# Board.net
KiCad netlist of a schematic drawn in EAGLE
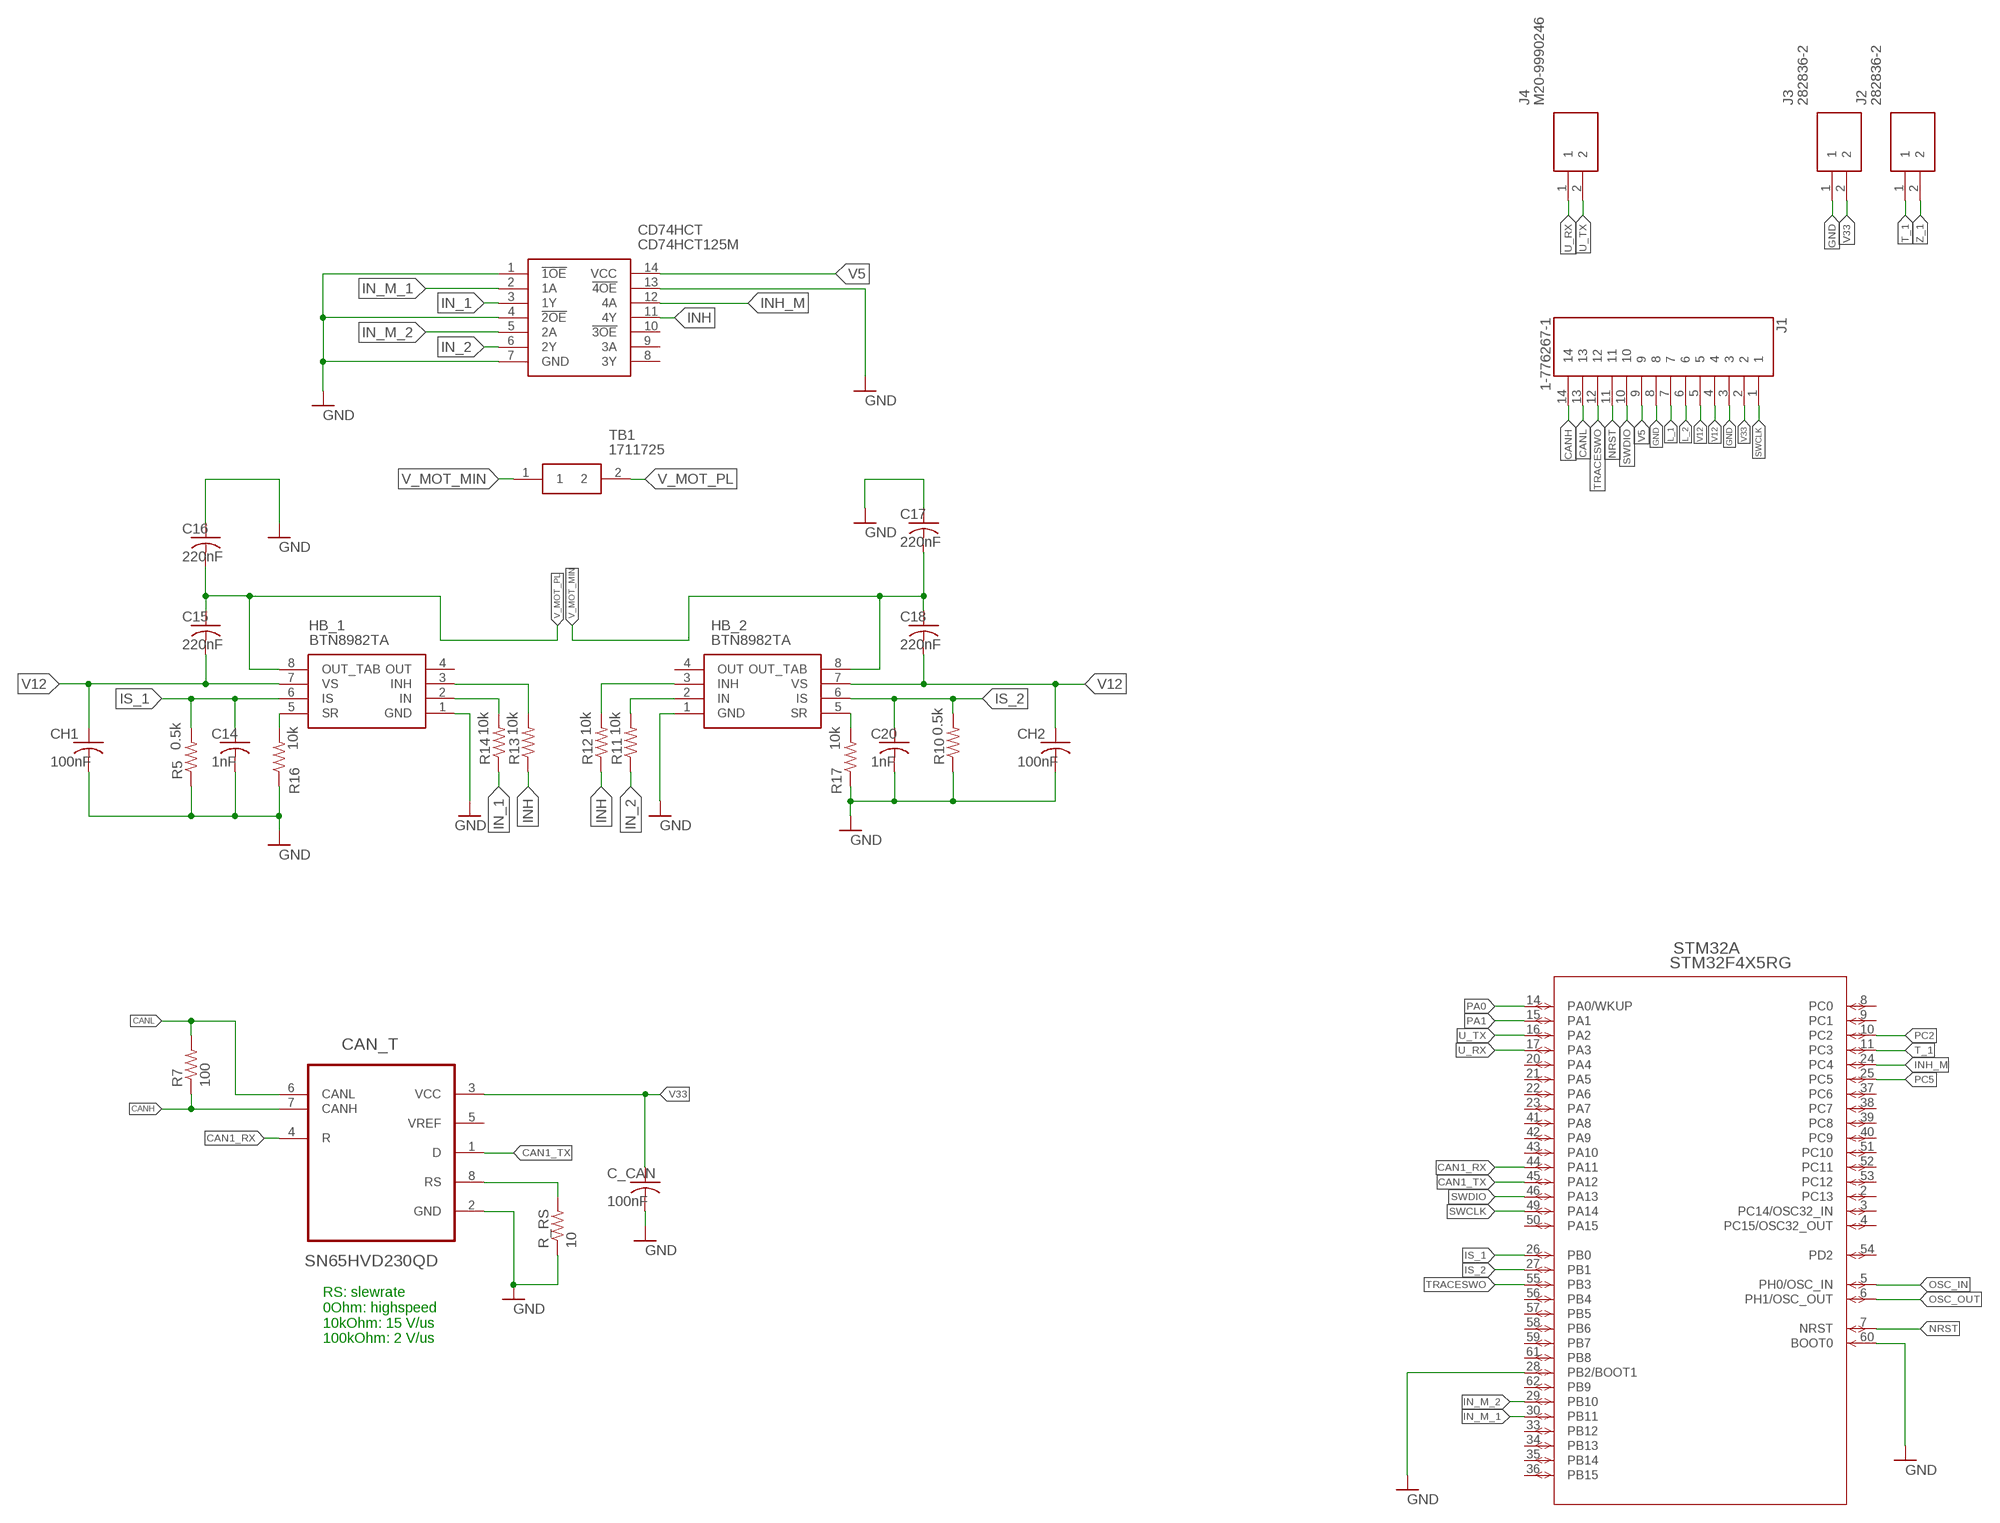
[diagram p0: schematic, sheet 1, part 1 of 2]
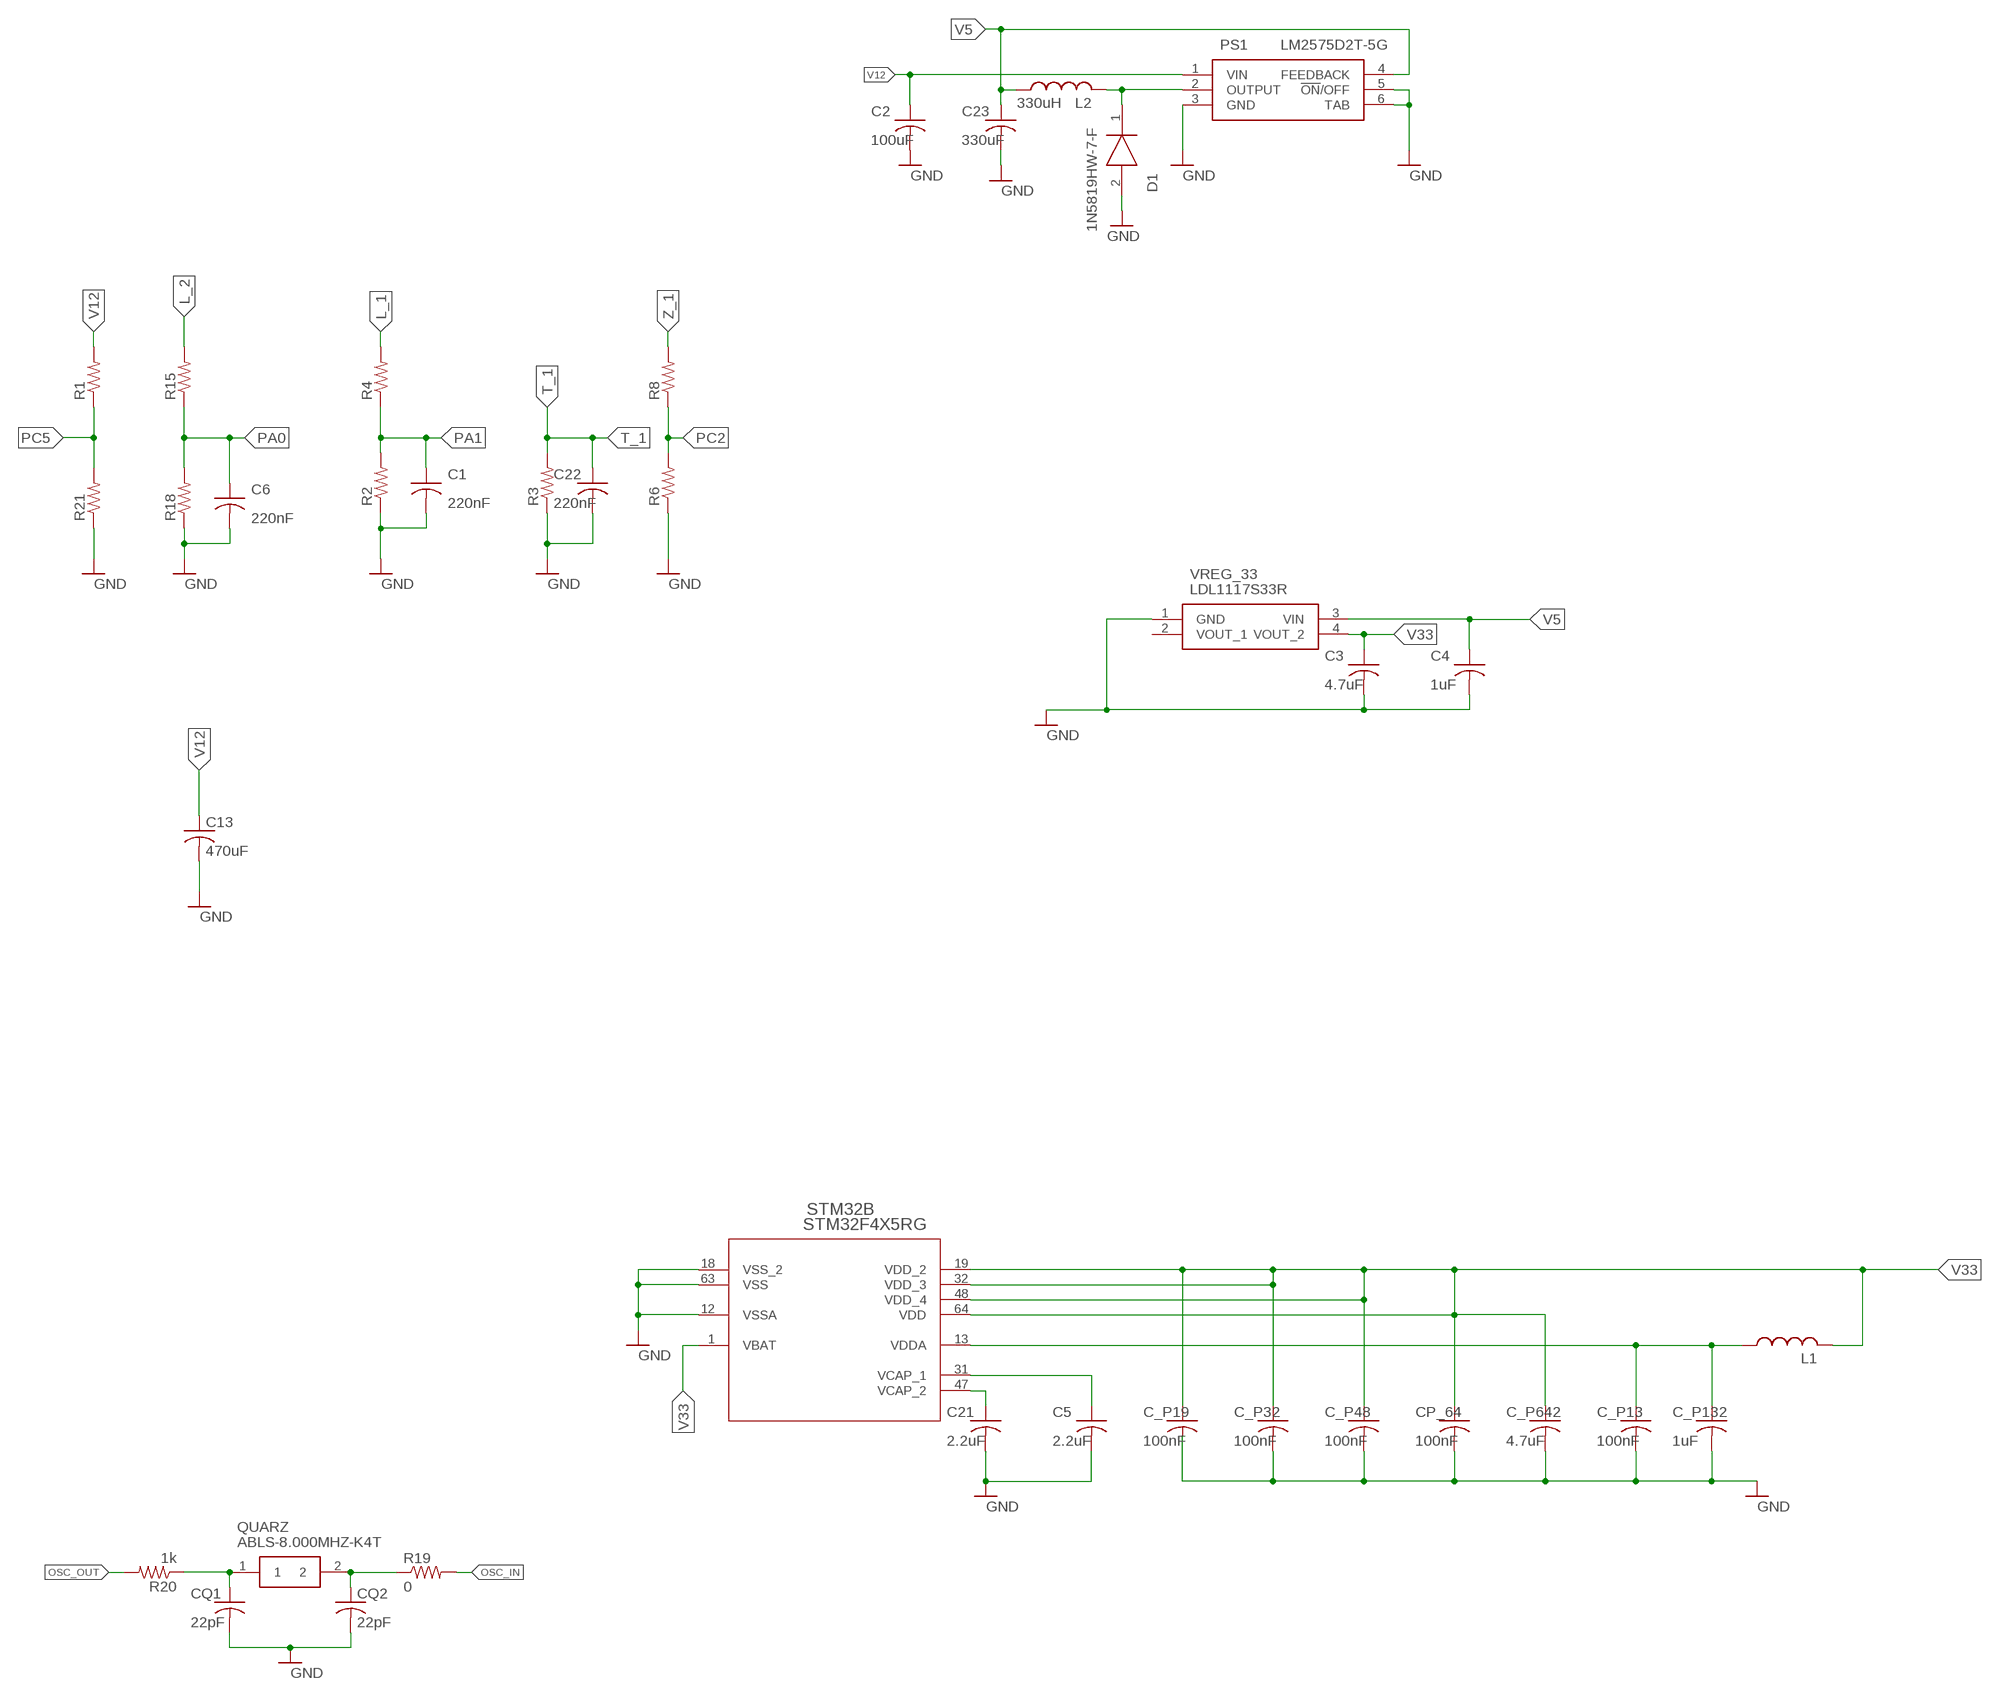
[diagram p1: schematic, sheet 1, part 2 of 2]

(export (version "E")
  (design (tool "Eeschema 10.0.6"))
  (components
    (comp (ref "C1")
      (value "220nF")
      (footprint "eagle-import:C0805")
      (libsource (lib "eagle-import") (part "C-USC0805"))
    )
    (comp (ref "C2")
      (value "100uF")
      (footprint "eagle-import:C0805")
      (libsource (lib "eagle-import") (part "C-USC0805"))
    )
    (comp (ref "C3")
      (value "4.7uF")
      (footprint "eagle-import:C0805")
      (libsource (lib "eagle-import") (part "C-USC0805"))
    )
    (comp (ref "C4")
      (value "1uF")
      (footprint "eagle-import:C0805")
      (libsource (lib "eagle-import") (part "C-USC0805"))
    )
    (comp (ref "C5")
      (value "2.2uF")
      (footprint "eagle-import:C0805")
      (libsource (lib "eagle-import") (part "C-USC0805"))
    )
    (comp (ref "C6")
      (value "220nF")
      (footprint "eagle-import:C0805")
      (libsource (lib "eagle-import") (part "C-USC0805"))
    )
    (comp (ref "C13")
      (value "470uF")
      (footprint "eagle-import:C050-075X075")
      (libsource (lib "eagle-import") (part "C-US050-075X075"))
    )
    (comp (ref "C14")
      (value "1nF")
      (footprint "eagle-import:C0805")
      (libsource (lib "eagle-import") (part "C-USC0805"))
    )
    (comp (ref "C15")
      (value "220nF")
      (footprint "eagle-import:C0805")
      (libsource (lib "eagle-import") (part "C-USC0805"))
    )
    (comp (ref "C16")
      (value "220nF")
      (footprint "eagle-import:C0805")
      (libsource (lib "eagle-import") (part "C-USC0805"))
    )
    (comp (ref "C17")
      (value "220nF")
      (footprint "eagle-import:C0805")
      (libsource (lib "eagle-import") (part "C-USC0805"))
    )
    (comp (ref "C18")
      (value "220nF")
      (footprint "eagle-import:C0805")
      (libsource (lib "eagle-import") (part "C-USC0805"))
    )
    (comp (ref "C20")
      (value "1nF")
      (footprint "eagle-import:C0805")
      (libsource (lib "eagle-import") (part "C-USC0805"))
    )
    (comp (ref "C21")
      (value "2.2uF")
      (footprint "eagle-import:C0805")
      (libsource (lib "eagle-import") (part "C-USC0805"))
    )
    (comp (ref "C22")
      (value "220nF")
      (footprint "eagle-import:C0805")
      (libsource (lib "eagle-import") (part "C-USC0805"))
    )
    (comp (ref "C23")
      (value "330uF")
      (footprint "eagle-import:C0805")
      (libsource (lib "eagle-import") (part "C-USC0805"))
    )
    (comp (ref "CAN_T")
      (value "SN65HVD230QD")
      (footprint "eagle-import:SOIC127P600X175-8N")
      (fields (field (name "MF") "TEXAS INSTRUMENTS") (field (name "MPN") "SN65HVD230QD.."))
      (libsource (lib "eagle-import") (part "SN65HVD230QD"))
    )
    (comp (ref "CD74HCT")
      (value "CD74HCT125M")
      (footprint "eagle-import:SOIC127P600X175-14N")
      (fields (field (name "MOUSER_PART_NUMBER") "595-CD74HCT125M"))
      (libsource (lib "eagle-import") (part "CD74HCT125M"))
    )
    (comp (ref "CH1")
      (value "100nF")
      (footprint "eagle-import:C0805")
      (libsource (lib "eagle-import") (part "C-USC0805"))
    )
    (comp (ref "CH2")
      (value "100nF")
      (footprint "eagle-import:C0805")
      (libsource (lib "eagle-import") (part "C-USC0805"))
    )
    (comp (ref "CP_64")
      (value "100nF")
      (footprint "eagle-import:C0805")
      (libsource (lib "eagle-import") (part "C-USC0805"))
    )
    (comp (ref "CQ1")
      (value "22pF")
      (footprint "eagle-import:C0805")
      (libsource (lib "eagle-import") (part "C-USC0805"))
    )
    (comp (ref "CQ2")
      (value "22pF")
      (footprint "eagle-import:C0805")
      (libsource (lib "eagle-import") (part "C-USC0805"))
    )
    (comp (ref "C_CAN")
      (value "100nF")
      (footprint "eagle-import:C0805")
      (libsource (lib "eagle-import") (part "C-USC0805"))
    )
    (comp (ref "C_P13")
      (value "100nF")
      (footprint "eagle-import:C0805")
      (libsource (lib "eagle-import") (part "C-USC0805"))
    )
    (comp (ref "C_P19")
      (value "100nF")
      (footprint "eagle-import:C0805")
      (libsource (lib "eagle-import") (part "C-USC0805"))
    )
    (comp (ref "C_P32")
      (value "100nF")
      (footprint "eagle-import:C0805")
      (libsource (lib "eagle-import") (part "C-USC0805"))
    )
    (comp (ref "C_P48")
      (value "100nF")
      (footprint "eagle-import:C0805")
      (libsource (lib "eagle-import") (part "C-USC0805"))
    )
    (comp (ref "C_P132")
      (value "1uF")
      (footprint "eagle-import:C0805")
      (libsource (lib "eagle-import") (part "C-USC0805"))
    )
    (comp (ref "C_P642")
      (value "4.7uF")
      (footprint "eagle-import:C0805")
      (libsource (lib "eagle-import") (part "C-USC0805"))
    )
    (comp (ref "D1")
      (value "1N5819HW-7-F")
      (footprint "eagle-import:SOD3716X145N")
      (fields (field (name "MOUSER_PART_NUMBER") "621-1N5819HW-F"))
      (libsource (lib "eagle-import") (part "1N5819HW-7-F"))
    )
    (comp (ref "HB_1")
      (value "BTN8982TA")
      (footprint "eagle-import:TO127P1500X440-8N")
      (fields (field (name "MOUSER_PART_NUMBER") "726-BTN8982TA"))
      (libsource (lib "eagle-import") (part "BTN8982TA"))
    )
    (comp (ref "HB_2")
      (value "BTN8982TA")
      (footprint "eagle-import:TO127P1500X440-8N")
      (fields (field (name "MOUSER_PART_NUMBER") "726-BTN8982TA"))
      (libsource (lib "eagle-import") (part "BTN8982TA"))
    )
    (comp (ref "J1")
      (value "1-776267-1")
      (footprint "eagle-import:TE_1-776267-1")
      (fields (field (name "DIGI-KEY_PART_NUMBER") "A142413-ND") (field (name "MF") "TE Connectivity"))
      (libsource (lib "eagle-import") (part "1-776267-1"))
    )
    (comp (ref "J2")
      (value "282836-2")
      (footprint "eagle-import:SHDR2W100P0X500_1X2_1000X820X1")
      (fields (field (name "MOUSER_PART_NUMBER") "571-2828362"))
      (libsource (lib "eagle-import") (part "282836-2"))
    )
    (comp (ref "J3")
      (value "282836-2")
      (footprint "eagle-import:SHDR2W100P0X500_1X2_1000X820X1")
      (fields (field (name "MOUSER_PART_NUMBER") "571-2828362"))
      (libsource (lib "eagle-import") (part "282836-2"))
    )
    (comp (ref "J4")
      (value "M20-9990246")
      (footprint "eagle-import:HDRV2W64P0X254_1X2_508X254X864")
      (fields (field (name "MOUSER_PART_NUMBER") "855-M20-9990246"))
      (libsource (lib "eagle-import") (part "M20-9990246"))
    )
    (comp (ref "L1")
      (value "INDUCTOR_0805_N")
      (footprint "eagle-import:RESC0805_N")
      (libsource (lib "eagle-import") (part "INDUCTOR_0805_N"))
    )
    (comp (ref "L2")
      (value "330uH")
      (footprint "eagle-import:RESC0805_N")
      (libsource (lib "eagle-import") (part "INDUCTOR_0805_N"))
    )
    (comp (ref "PS1")
      (value "LM2575D2T-5G")
      (footprint "eagle-import:D2TSUFFIX-CASE936A-02-ISSUEC")
      (fields (field (name "MOUSER_PART_NUMBER") "863-LM2575D2T-5G"))
      (libsource (lib "eagle-import") (part "LM2575D2T-5G"))
    )
    (comp (ref "QUARZ")
      (value "ABLS-8.000MHZ-K4T")
      (footprint "eagle-import:ABLS-12.000MHZ-B2")
      (fields (field (name "MOUSER_PART_NUMBER") "815-ABLS-8.0MK4-T") (field (name "MF") "ABRACON"))
      (libsource (lib "eagle-import") (part "ABLS-8.000MHZ-K4T"))
    )
    (comp (ref "R1")
      (value "R-US_R0805")
      (footprint "eagle-import:R0805")
      (libsource (lib "eagle-import") (part "R-US_R0805"))
    )
    (comp (ref "R2")
      (value "R-US_R0805")
      (footprint "eagle-import:R0805")
      (libsource (lib "eagle-import") (part "R-US_R0805"))
    )
    (comp (ref "R3")
      (value "R-US_R0805")
      (footprint "eagle-import:R0805")
      (libsource (lib "eagle-import") (part "R-US_R0805"))
    )
    (comp (ref "R4")
      (value "R-US_R0805")
      (footprint "eagle-import:R0805")
      (libsource (lib "eagle-import") (part "R-US_R0805"))
    )
    (comp (ref "R5")
      (value "0.5k")
      (footprint "eagle-import:R0805")
      (libsource (lib "eagle-import") (part "R-US_R0805"))
    )
    (comp (ref "R6")
      (value "R-US_R0805")
      (footprint "eagle-import:R0805")
      (libsource (lib "eagle-import") (part "R-US_R0805"))
    )
    (comp (ref "R7")
      (value "100")
      (footprint "eagle-import:R0805")
      (libsource (lib "eagle-import") (part "R-US_R0805"))
    )
    (comp (ref "R8")
      (value "R-US_R0805")
      (footprint "eagle-import:R0805")
      (libsource (lib "eagle-import") (part "R-US_R0805"))
    )
    (comp (ref "R10")
      (value "0.5k")
      (footprint "eagle-import:R0805")
      (libsource (lib "eagle-import") (part "R-US_R0805"))
    )
    (comp (ref "R11")
      (value "10k")
      (footprint "eagle-import:R0805")
      (libsource (lib "eagle-import") (part "R-US_R0805"))
    )
    (comp (ref "R12")
      (value "10k")
      (footprint "eagle-import:R0805")
      (libsource (lib "eagle-import") (part "R-US_R0805"))
    )
    (comp (ref "R13")
      (value "10k")
      (footprint "eagle-import:R0805")
      (libsource (lib "eagle-import") (part "R-US_R0805"))
    )
    (comp (ref "R14")
      (value "10k")
      (footprint "eagle-import:R0805")
      (libsource (lib "eagle-import") (part "R-US_R0805"))
    )
    (comp (ref "R15")
      (value "R-US_R0805")
      (footprint "eagle-import:R0805")
      (libsource (lib "eagle-import") (part "R-US_R0805"))
    )
    (comp (ref "R16")
      (value "10k")
      (footprint "eagle-import:R0805")
      (libsource (lib "eagle-import") (part "resistor_348_R-US_R0805"))
    )
    (comp (ref "R17")
      (value "10k")
      (footprint "eagle-import:R0805")
      (libsource (lib "eagle-import") (part "resistor_348_R-US_R0805"))
    )
    (comp (ref "R18")
      (value "R-US_R0805")
      (footprint "eagle-import:R0805")
      (libsource (lib "eagle-import") (part "R-US_R0805"))
    )
    (comp (ref "R19")
      (value "0")
      (footprint "eagle-import:R0805")
      (libsource (lib "eagle-import") (part "resistor_348_R-US_R0805"))
    )
    (comp (ref "R20")
      (value "1k")
      (footprint "eagle-import:R0805")
      (libsource (lib "eagle-import") (part "resistor_348_R-US_R0805"))
    )
    (comp (ref "R21")
      (value "R-US_R0805")
      (footprint "eagle-import:R0805")
      (libsource (lib "eagle-import") (part "R-US_R0805"))
    )
    (comp (ref "R_RS")
      (value "10")
      (footprint "eagle-import:R0805")
      (libsource (lib "eagle-import") (part "R-US_R0805"))
    )
    (comp (ref "STM32")
      (value "STM32F4X5RG")
      (footprint "eagle-import:LQFP64-10X10MM")
      (fields (field (name "OC_FARNELL") "unknown"))
      (libsource (lib "eagle-import") (part "STM32F4X5RG"))
    )
    (comp (ref "TB1")
      (value "1711725")
      (footprint "eagle-import:PHEONIX-5.08PITCH-2PIN")
      (fields (field (name "MOUSER_PART_NUMBER") "651-1711725"))
      (libsource (lib "eagle-import") (part "1711725"))
    )
    (comp (ref "VREG_33")
      (value "LDL1117S33R")
      (footprint "eagle-import:SOT230P700X180-4N")
      (fields (field (name "MOUSER_PART_NUMBER") "511-LDL1117S33R") (field (name "MF") "STMICROELECTRONICS"))
      (libsource (lib "eagle-import") (part "LDL1117S33R"))
    )
  )
  (nets
    (net (code "1") (name "CAN1_RX") (class "Default")
      (node (ref "CAN_T") (pin "4") (pinfunction "R_4") (pintype "output"))
      (node (ref "STM32") (pin "44") (pinfunction "PA11_44") (pintype "bidirectional"))
    )
    (net (code "2") (name "CAN1_TX") (class "Default")
      (node (ref "CAN_T") (pin "1") (pinfunction "D_1") (pintype "input"))
      (node (ref "STM32") (pin "45") (pinfunction "PA12_45") (pintype "bidirectional"))
    )
    (net (code "3") (name "CANH") (class "Default")
      (node (ref "CAN_T") (pin "7") (pinfunction "CANH_7") (pintype "output"))
      (node (ref "J1") (pin "14") (pinfunction "14_14") (pintype "passive"))
      (node (ref "R7") (pin "1") (pinfunction "1_1") (pintype "passive"))
    )
    (net (code "4") (name "CANL") (class "Default")
      (node (ref "CAN_T") (pin "6") (pinfunction "CANL_6") (pintype "output"))
      (node (ref "J1") (pin "13") (pinfunction "13_13") (pintype "passive"))
      (node (ref "R7") (pin "2") (pinfunction "2_2") (pintype "passive"))
    )
    (net (code "5") (name "GND") (class "Default")
      (node (ref "C1") (pin "2") (pinfunction "2_2") (pintype "passive"))
      (node (ref "C13") (pin "2") (pinfunction "2_2") (pintype "passive"))
      (node (ref "C14") (pin "2") (pinfunction "2_2") (pintype "passive"))
      (node (ref "C16") (pin "1") (pinfunction "1_1") (pintype "passive"))
      (node (ref "C17") (pin "1") (pinfunction "1_1") (pintype "passive"))
      (node (ref "C2") (pin "2") (pinfunction "2_2") (pintype "passive"))
      (node (ref "C20") (pin "2") (pinfunction "2_2") (pintype "passive"))
      (node (ref "C21") (pin "2") (pinfunction "2_2") (pintype "passive"))
      (node (ref "C22") (pin "2") (pinfunction "2_2") (pintype "passive"))
      (node (ref "C23") (pin "2") (pinfunction "2_2") (pintype "passive"))
      (node (ref "C3") (pin "2") (pinfunction "2_2") (pintype "passive"))
      (node (ref "C4") (pin "2") (pinfunction "2_2") (pintype "passive"))
      (node (ref "C5") (pin "2") (pinfunction "2_2") (pintype "passive"))
      (node (ref "C6") (pin "2") (pinfunction "2_2") (pintype "passive"))
      (node (ref "CAN_T") (pin "2") (pinfunction "GND_2") (pintype "passive"))
      (node (ref "CD74HCT") (pin "1") (pinfunction "~{1OE}_1") (pintype "bidirectional"))
      (node (ref "CD74HCT") (pin "13") (pinfunction "~{4OE}_13") (pintype "bidirectional"))
      (node (ref "CD74HCT") (pin "4") (pinfunction "~{2OE}_4") (pintype "bidirectional"))
      (node (ref "CD74HCT") (pin "7") (pinfunction "GND_7") (pintype "power_in"))
      (node (ref "CH1") (pin "2") (pinfunction "2_2") (pintype "passive"))
      (node (ref "CH2") (pin "2") (pinfunction "2_2") (pintype "passive"))
      (node (ref "CP_64") (pin "2") (pinfunction "2_2") (pintype "passive"))
      (node (ref "CQ1") (pin "2") (pinfunction "2_2") (pintype "passive"))
      (node (ref "CQ2") (pin "2") (pinfunction "2_2") (pintype "passive"))
      (node (ref "C_CAN") (pin "2") (pinfunction "2_2") (pintype "passive"))
      (node (ref "C_P13") (pin "2") (pinfunction "2_2") (pintype "passive"))
      (node (ref "C_P132") (pin "2") (pinfunction "2_2") (pintype "passive"))
      (node (ref "C_P19") (pin "2") (pinfunction "2_2") (pintype "passive"))
      (node (ref "C_P32") (pin "2") (pinfunction "2_2") (pintype "passive"))
      (node (ref "C_P48") (pin "2") (pinfunction "2_2") (pintype "passive"))
      (node (ref "C_P642") (pin "2") (pinfunction "2_2") (pintype "passive"))
      (node (ref "D1") (pin "2") (pinfunction "A_2") (pintype "bidirectional"))
      (node (ref "HB_1") (pin "1") (pinfunction "GND_1") (pintype "power_in"))
      (node (ref "HB_2") (pin "1") (pinfunction "GND_1") (pintype "power_in"))
      (node (ref "J1") (pin "3") (pinfunction "3_3") (pintype "passive"))
      (node (ref "J1") (pin "8") (pinfunction "8_8") (pintype "passive"))
      (node (ref "J3") (pin "1") (pinfunction "1_1") (pintype "bidirectional"))
      (node (ref "PS1") (pin "3") (pinfunction "GND_3") (pintype "bidirectional"))
      (node (ref "PS1") (pin "5") (pinfunction "~{ON}/OFF_5") (pintype "bidirectional"))
      (node (ref "PS1") (pin "6") (pinfunction "TAB_6") (pintype "bidirectional"))
      (node (ref "R10") (pin "1") (pinfunction "1_1") (pintype "passive"))
      (node (ref "R16") (pin "1") (pinfunction "1_1") (pintype "passive"))
      (node (ref "R17") (pin "1") (pinfunction "1_1") (pintype "passive"))
      (node (ref "R18") (pin "1") (pinfunction "1_1") (pintype "passive"))
      (node (ref "R2") (pin "1") (pinfunction "1_1") (pintype "passive"))
      (node (ref "R21") (pin "1") (pinfunction "1_1") (pintype "passive"))
      (node (ref "R3") (pin "1") (pinfunction "1_1") (pintype "passive"))
      (node (ref "R5") (pin "1") (pinfunction "1_1") (pintype "passive"))
      (node (ref "R6") (pin "1") (pinfunction "1_1") (pintype "passive"))
      (node (ref "R_RS") (pin "1") (pinfunction "1_1") (pintype "passive"))
      (node (ref "STM32") (pin "12") (pinfunction "VSSA_12") (pintype "power_in"))
      (node (ref "STM32") (pin "18") (pinfunction "VSS_2_18") (pintype "power_in"))
      (node (ref "STM32") (pin "28") (pinfunction "PB2/BOOT1_28") (pintype "bidirectional"))
      (node (ref "STM32") (pin "60") (pinfunction "BOOT0_60") (pintype "input"))
      (node (ref "STM32") (pin "63") (pinfunction "VSS_63") (pintype "power_in"))
      (node (ref "VREG_33") (pin "1") (pinfunction "GND_1") (pintype "power_in"))
    )
    (net (code "6") (name "INH") (class "Default")
      (node (ref "CD74HCT") (pin "11") (pinfunction "4Y_11") (pintype "bidirectional"))
      (node (ref "R12") (pin "1") (pinfunction "1_1") (pintype "passive"))
      (node (ref "R13") (pin "1") (pinfunction "1_1") (pintype "passive"))
    )
    (net (code "7") (name "INH_M") (class "Default")
      (node (ref "CD74HCT") (pin "12") (pinfunction "4A_12") (pintype "bidirectional"))
      (node (ref "STM32") (pin "24") (pinfunction "PC4_24") (pintype "bidirectional"))
    )
    (net (code "8") (name "IN_1") (class "Default")
      (node (ref "CD74HCT") (pin "3") (pinfunction "1Y_3") (pintype "bidirectional"))
      (node (ref "R14") (pin "1") (pinfunction "1_1") (pintype "passive"))
    )
    (net (code "9") (name "IN_2") (class "Default")
      (node (ref "CD74HCT") (pin "6") (pinfunction "2Y_6") (pintype "bidirectional"))
      (node (ref "R11") (pin "1") (pinfunction "1_1") (pintype "passive"))
    )
    (net (code "10") (name "IN_M_1") (class "Default")
      (node (ref "CD74HCT") (pin "2") (pinfunction "1A_2") (pintype "bidirectional"))
      (node (ref "STM32") (pin "30") (pinfunction "PB11_30") (pintype "bidirectional"))
    )
    (net (code "11") (name "IN_M_2") (class "Default")
      (node (ref "CD74HCT") (pin "5") (pinfunction "2A_5") (pintype "bidirectional"))
      (node (ref "STM32") (pin "29") (pinfunction "PB10_29") (pintype "bidirectional"))
    )
    (net (code "12") (name "IS_1") (class "Default")
      (node (ref "C14") (pin "1") (pinfunction "1_1") (pintype "passive"))
      (node (ref "HB_1") (pin "6") (pinfunction "IS_6") (pintype "bidirectional"))
      (node (ref "R5") (pin "2") (pinfunction "2_2") (pintype "passive"))
      (node (ref "STM32") (pin "26") (pinfunction "PB0_26") (pintype "bidirectional"))
    )
    (net (code "13") (name "IS_2") (class "Default")
      (node (ref "C20") (pin "1") (pinfunction "1_1") (pintype "passive"))
      (node (ref "HB_2") (pin "6") (pinfunction "IS_6") (pintype "bidirectional"))
      (node (ref "R10") (pin "2") (pinfunction "2_2") (pintype "passive"))
      (node (ref "STM32") (pin "27") (pinfunction "PB1_27") (pintype "bidirectional"))
    )
    (net (code "14") (name "L_1") (class "Default")
      (node (ref "J1") (pin "7") (pinfunction "7_7") (pintype "passive"))
      (node (ref "R4") (pin "2") (pinfunction "2_2") (pintype "passive"))
    )
    (net (code "15") (name "L_2") (class "Default")
      (node (ref "J1") (pin "6") (pinfunction "6_6") (pintype "passive"))
      (node (ref "R15") (pin "2") (pinfunction "2_2") (pintype "passive"))
    )
    (net (code "16") (name "NRST") (class "Default")
      (node (ref "J1") (pin "11") (pinfunction "11_11") (pintype "passive"))
      (node (ref "STM32") (pin "7") (pinfunction "NRST_7") (pintype "bidirectional"))
    )
    (net (code "17") (name "Net-(CAN_T-RS)") (class "Default")
      (node (ref "CAN_T") (pin "8") (pinfunction "RS_8") (pintype "input"))
      (node (ref "R_RS") (pin "2") (pinfunction "2_2") (pintype "passive"))
    )
    (net (code "18") (name "Net-(CQ1-Pad1)") (class "Default")
      (node (ref "CQ1") (pin "1") (pinfunction "1_1") (pintype "passive"))
      (node (ref "QUARZ") (pin "1") (pinfunction "1_1") (pintype "bidirectional"))
      (node (ref "R20") (pin "1") (pinfunction "1_1") (pintype "passive"))
    )
    (net (code "19") (name "Net-(CQ2-Pad1)") (class "Default")
      (node (ref "CQ2") (pin "1") (pinfunction "1_1") (pintype "passive"))
      (node (ref "QUARZ") (pin "2") (pinfunction "2_2") (pintype "bidirectional"))
      (node (ref "R19") (pin "1") (pinfunction "1_1") (pintype "passive"))
    )
    (net (code "20") (name "Net-(D1-K)") (class "Default")
      (node (ref "D1") (pin "1") (pinfunction "K_1") (pintype "bidirectional"))
      (node (ref "L2") (pin "2") (pinfunction "2_2") (pintype "passive"))
      (node (ref "PS1") (pin "2") (pinfunction "OUTPUT_2") (pintype "bidirectional"))
    )
    (net (code "21") (name "Net-(HB_1-IN)") (class "Default")
      (node (ref "HB_1") (pin "2") (pinfunction "IN_2") (pintype "input"))
      (node (ref "R14") (pin "2") (pinfunction "2_2") (pintype "passive"))
    )
    (net (code "22") (name "Net-(HB_1-INH)") (class "Default")
      (node (ref "HB_1") (pin "3") (pinfunction "INH_3") (pintype "input"))
      (node (ref "R13") (pin "2") (pinfunction "2_2") (pintype "passive"))
    )
    (net (code "23") (name "Net-(HB_1-SR)") (class "Default")
      (node (ref "HB_1") (pin "5") (pinfunction "SR_5") (pintype "bidirectional"))
      (node (ref "R16") (pin "2") (pinfunction "2_2") (pintype "passive"))
    )
    (net (code "24") (name "Net-(HB_2-IN)") (class "Default")
      (node (ref "HB_2") (pin "2") (pinfunction "IN_2") (pintype "input"))
      (node (ref "R11") (pin "2") (pinfunction "2_2") (pintype "passive"))
    )
    (net (code "25") (name "Net-(HB_2-INH)") (class "Default")
      (node (ref "HB_2") (pin "3") (pinfunction "INH_3") (pintype "input"))
      (node (ref "R12") (pin "2") (pinfunction "2_2") (pintype "passive"))
    )
    (net (code "26") (name "Net-(HB_2-SR)") (class "Default")
      (node (ref "HB_2") (pin "5") (pinfunction "SR_5") (pintype "bidirectional"))
      (node (ref "R17") (pin "2") (pinfunction "2_2") (pintype "passive"))
    )
    (net (code "27") (name "Net-(STM32B-VCAP_1)") (class "Default")
      (node (ref "C5") (pin "1") (pinfunction "1_1") (pintype "passive"))
      (node (ref "STM32") (pin "31") (pinfunction "VCAP_1_31") (pintype "power_in"))
    )
    (net (code "28") (name "Net-(STM32B-VCAP_2)") (class "Default")
      (node (ref "C21") (pin "1") (pinfunction "1_1") (pintype "passive"))
      (node (ref "STM32") (pin "47") (pinfunction "VCAP_2_47") (pintype "power_in"))
    )
    (net (code "29") (name "Net-(STM32B-VDDA)") (class "Default")
      (node (ref "C_P13") (pin "1") (pinfunction "1_1") (pintype "passive"))
      (node (ref "C_P132") (pin "1") (pinfunction "1_1") (pintype "passive"))
      (node (ref "L1") (pin "1") (pinfunction "1_1") (pintype "passive"))
      (node (ref "STM32") (pin "13") (pinfunction "VDDA_13") (pintype "power_in"))
    )
    (net (code "30") (name "OSC_IN") (class "Default")
      (node (ref "R19") (pin "2") (pinfunction "2_2") (pintype "passive"))
      (node (ref "STM32") (pin "5") (pinfunction "PH0/OSC_IN_5") (pintype "bidirectional"))
    )
    (net (code "31") (name "OSC_OUT") (class "Default")
      (node (ref "R20") (pin "2") (pinfunction "2_2") (pintype "passive"))
      (node (ref "STM32") (pin "6") (pinfunction "PH1/OSC_OUT_6") (pintype "bidirectional"))
    )
    (net (code "32") (name "PA0") (class "Default")
      (node (ref "C6") (pin "1") (pinfunction "1_1") (pintype "passive"))
      (node (ref "R15") (pin "1") (pinfunction "1_1") (pintype "passive"))
      (node (ref "R18") (pin "2") (pinfunction "2_2") (pintype "passive"))
      (node (ref "STM32") (pin "14") (pinfunction "PA0/WKUP_14") (pintype "bidirectional"))
    )
    (net (code "33") (name "PA1") (class "Default")
      (node (ref "C1") (pin "1") (pinfunction "1_1") (pintype "passive"))
      (node (ref "R2") (pin "2") (pinfunction "2_2") (pintype "passive"))
      (node (ref "R4") (pin "1") (pinfunction "1_1") (pintype "passive"))
      (node (ref "STM32") (pin "15") (pinfunction "PA1_15") (pintype "bidirectional"))
    )
    (net (code "34") (name "PC2") (class "Default")
      (node (ref "R6") (pin "2") (pinfunction "2_2") (pintype "passive"))
      (node (ref "R8") (pin "1") (pinfunction "1_1") (pintype "passive"))
      (node (ref "STM32") (pin "10") (pinfunction "PC2_10") (pintype "bidirectional"))
    )
    (net (code "35") (name "PC5") (class "Default")
      (node (ref "R1") (pin "1") (pinfunction "1_1") (pintype "passive"))
      (node (ref "R21") (pin "2") (pinfunction "2_2") (pintype "passive"))
      (node (ref "STM32") (pin "25") (pinfunction "PC5_25") (pintype "bidirectional"))
    )
    (net (code "36") (name "SWCLK") (class "Default")
      (node (ref "J1") (pin "1") (pinfunction "1_1") (pintype "passive"))
      (node (ref "STM32") (pin "49") (pinfunction "PA14_49") (pintype "bidirectional"))
    )
    (net (code "37") (name "SWDIO") (class "Default")
      (node (ref "J1") (pin "10") (pinfunction "10_10") (pintype "passive"))
      (node (ref "STM32") (pin "46") (pinfunction "PA13_46") (pintype "bidirectional"))
    )
    (net (code "38") (name "TRACESWO") (class "Default")
      (node (ref "J1") (pin "12") (pinfunction "12_12") (pintype "passive"))
      (node (ref "STM32") (pin "55") (pinfunction "PB3_55") (pintype "bidirectional"))
    )
    (net (code "39") (name "T_1") (class "Default")
      (node (ref "C22") (pin "1") (pinfunction "1_1") (pintype "passive"))
      (node (ref "J2") (pin "1") (pinfunction "1_1") (pintype "bidirectional"))
      (node (ref "R3") (pin "2") (pinfunction "2_2") (pintype "passive"))
      (node (ref "STM32") (pin "11") (pinfunction "PC3_11") (pintype "bidirectional"))
    )
    (net (code "40") (name "U_RX") (class "Default")
      (node (ref "J4") (pin "1") (pinfunction "1_1") (pintype "bidirectional"))
      (node (ref "STM32") (pin "17") (pinfunction "PA3_17") (pintype "bidirectional"))
    )
    (net (code "41") (name "U_TX") (class "Default")
      (node (ref "J4") (pin "2") (pinfunction "2_2") (pintype "bidirectional"))
      (node (ref "STM32") (pin "16") (pinfunction "PA2_16") (pintype "bidirectional"))
    )
    (net (code "42") (name "V5") (class "Default")
      (node (ref "C23") (pin "1") (pinfunction "1_1") (pintype "passive"))
      (node (ref "C4") (pin "1") (pinfunction "1_1") (pintype "passive"))
      (node (ref "CD74HCT") (pin "14") (pinfunction "VCC_14") (pintype "power_in"))
      (node (ref "J1") (pin "9") (pinfunction "9_9") (pintype "passive"))
      (node (ref "L2") (pin "1") (pinfunction "1_1") (pintype "passive"))
      (node (ref "PS1") (pin "4") (pinfunction "FEEDBACK_4") (pintype "bidirectional"))
      (node (ref "VREG_33") (pin "3") (pinfunction "VIN_3") (pintype "input"))
    )
    (net (code "43") (name "V12") (class "Default")
      (node (ref "C13") (pin "1") (pinfunction "1_1") (pintype "passive"))
      (node (ref "C15") (pin "2") (pinfunction "2_2") (pintype "passive"))
      (node (ref "C18") (pin "2") (pinfunction "2_2") (pintype "passive"))
      (node (ref "C2") (pin "1") (pinfunction "1_1") (pintype "passive"))
      (node (ref "CH1") (pin "1") (pinfunction "1_1") (pintype "passive"))
      (node (ref "CH2") (pin "1") (pinfunction "1_1") (pintype "passive"))
      (node (ref "HB_1") (pin "7") (pinfunction "VS_7") (pintype "bidirectional"))
      (node (ref "HB_2") (pin "7") (pinfunction "VS_7") (pintype "bidirectional"))
      (node (ref "J1") (pin "4") (pinfunction "4_4") (pintype "passive"))
      (node (ref "J1") (pin "5") (pinfunction "5_5") (pintype "passive"))
      (node (ref "PS1") (pin "1") (pinfunction "VIN_1") (pintype "bidirectional"))
      (node (ref "R1") (pin "2") (pinfunction "2_2") (pintype "passive"))
    )
    (net (code "44") (name "V33") (class "Default")
      (node (ref "C3") (pin "1") (pinfunction "1_1") (pintype "passive"))
      (node (ref "CAN_T") (pin "3") (pinfunction "VCC_3") (pintype "power_in"))
      (node (ref "CP_64") (pin "1") (pinfunction "1_1") (pintype "passive"))
      (node (ref "C_CAN") (pin "1") (pinfunction "1_1") (pintype "passive"))
      (node (ref "C_P19") (pin "1") (pinfunction "1_1") (pintype "passive"))
      (node (ref "C_P32") (pin "1") (pinfunction "1_1") (pintype "passive"))
      (node (ref "C_P48") (pin "1") (pinfunction "1_1") (pintype "passive"))
      (node (ref "C_P642") (pin "1") (pinfunction "1_1") (pintype "passive"))
      (node (ref "J1") (pin "2") (pinfunction "2_2") (pintype "passive"))
      (node (ref "J3") (pin "2") (pinfunction "2_2") (pintype "bidirectional"))
      (node (ref "L1") (pin "2") (pinfunction "2_2") (pintype "passive"))
      (node (ref "STM32") (pin "1") (pinfunction "VBAT_1") (pintype "power_in"))
      (node (ref "STM32") (pin "19") (pinfunction "VDD_2_19") (pintype "power_in"))
      (node (ref "STM32") (pin "32") (pinfunction "VDD_3_32") (pintype "power_in"))
      (node (ref "STM32") (pin "48") (pinfunction "VDD_4_48") (pintype "power_in"))
      (node (ref "STM32") (pin "64") (pinfunction "VDD_64") (pintype "power_in"))
      (node (ref "VREG_33") (pin "4") (pinfunction "VOUT_2_4") (pintype "output"))
    )
    (net (code "45") (name "V_MOT_MIN") (class "Default")
      (node (ref "C17") (pin "2") (pinfunction "2_2") (pintype "passive"))
      (node (ref "C18") (pin "1") (pinfunction "1_1") (pintype "passive"))
      (node (ref "HB_2") (pin "8") (pinfunction "OUT_TAB_8") (pintype "output"))
      (node (ref "TB1") (pin "1") (pinfunction "1_1") (pintype "bidirectional"))
    )
    (net (code "46") (name "V_MOT_PL") (class "Default")
      (node (ref "C15") (pin "1") (pinfunction "1_1") (pintype "passive"))
      (node (ref "C16") (pin "2") (pinfunction "2_2") (pintype "passive"))
      (node (ref "HB_1") (pin "8") (pinfunction "OUT_TAB_8") (pintype "output"))
      (node (ref "TB1") (pin "2") (pinfunction "2_2") (pintype "bidirectional"))
    )
    (net (code "47") (name "Z_1") (class "Default")
      (node (ref "J2") (pin "2") (pinfunction "2_2") (pintype "bidirectional"))
      (node (ref "R8") (pin "2") (pinfunction "2_2") (pintype "passive"))
    )
    (net (code "48") (name "unconnected-(CAN_T-VREF-Pad5)") (class "Default")
      (node (ref "CAN_T") (pin "5") (pinfunction "VREF_5") (pintype "input"))
    )
    (net (code "49") (name "unconnected-(CD74HCT-3A-Pad9)") (class "Default")
      (node (ref "CD74HCT") (pin "9") (pinfunction "3A_9") (pintype "bidirectional"))
    )
    (net (code "50") (name "unconnected-(CD74HCT-3Y-Pad8)") (class "Default")
      (node (ref "CD74HCT") (pin "8") (pinfunction "3Y_8") (pintype "bidirectional"))
    )
    (net (code "51") (name "unconnected-(CD74HCT-~{3OE}-Pad10)") (class "Default")
      (node (ref "CD74HCT") (pin "10") (pinfunction "~{3OE}_10") (pintype "bidirectional"))
    )
    (net (code "52") (name "unconnected-(HB_1-OUT-Pad4)") (class "Default")
      (node (ref "HB_1") (pin "4") (pinfunction "OUT_4") (pintype "output"))
    )
    (net (code "53") (name "unconnected-(HB_2-OUT-Pad4)") (class "Default")
      (node (ref "HB_2") (pin "4") (pinfunction "OUT_4") (pintype "output"))
    )
    (net (code "54") (name "unconnected-(STM32A-PA4-Pad20)") (class "Default")
      (node (ref "STM32") (pin "20") (pinfunction "PA4_20") (pintype "bidirectional"))
    )
    (net (code "55") (name "unconnected-(STM32A-PA5-Pad21)") (class "Default")
      (node (ref "STM32") (pin "21") (pinfunction "PA5_21") (pintype "bidirectional"))
    )
    (net (code "56") (name "unconnected-(STM32A-PA6-Pad22)") (class "Default")
      (node (ref "STM32") (pin "22") (pinfunction "PA6_22") (pintype "bidirectional"))
    )
    (net (code "57") (name "unconnected-(STM32A-PA7-Pad23)") (class "Default")
      (node (ref "STM32") (pin "23") (pinfunction "PA7_23") (pintype "bidirectional"))
    )
    (net (code "58") (name "unconnected-(STM32A-PA8-Pad41)") (class "Default")
      (node (ref "STM32") (pin "41") (pinfunction "PA8_41") (pintype "bidirectional"))
    )
    (net (code "59") (name "unconnected-(STM32A-PA9-Pad42)") (class "Default")
      (node (ref "STM32") (pin "42") (pinfunction "PA9_42") (pintype "bidirectional"))
    )
    (net (code "60") (name "unconnected-(STM32A-PA10-Pad43)") (class "Default")
      (node (ref "STM32") (pin "43") (pinfunction "PA10_43") (pintype "bidirectional"))
    )
    (net (code "61") (name "unconnected-(STM32A-PA15-Pad50)") (class "Default")
      (node (ref "STM32") (pin "50") (pinfunction "PA15_50") (pintype "bidirectional"))
    )
    (net (code "62") (name "unconnected-(STM32A-PB4-Pad56)") (class "Default")
      (node (ref "STM32") (pin "56") (pinfunction "PB4_56") (pintype "bidirectional"))
    )
    (net (code "63") (name "unconnected-(STM32A-PB5-Pad57)") (class "Default")
      (node (ref "STM32") (pin "57") (pinfunction "PB5_57") (pintype "bidirectional"))
    )
    (net (code "64") (name "unconnected-(STM32A-PB6-Pad58)") (class "Default")
      (node (ref "STM32") (pin "58") (pinfunction "PB6_58") (pintype "bidirectional"))
    )
    (net (code "65") (name "unconnected-(STM32A-PB7-Pad59)") (class "Default")
      (node (ref "STM32") (pin "59") (pinfunction "PB7_59") (pintype "bidirectional"))
    )
    (net (code "66") (name "unconnected-(STM32A-PB8-Pad61)") (class "Default")
      (node (ref "STM32") (pin "61") (pinfunction "PB8_61") (pintype "bidirectional"))
    )
    (net (code "67") (name "unconnected-(STM32A-PB9-Pad62)") (class "Default")
      (node (ref "STM32") (pin "62") (pinfunction "PB9_62") (pintype "bidirectional"))
    )
    (net (code "68") (name "unconnected-(STM32A-PB12-Pad33)") (class "Default")
      (node (ref "STM32") (pin "33") (pinfunction "PB12_33") (pintype "bidirectional"))
    )
    (net (code "69") (name "unconnected-(STM32A-PB13-Pad34)") (class "Default")
      (node (ref "STM32") (pin "34") (pinfunction "PB13_34") (pintype "bidirectional"))
    )
    (net (code "70") (name "unconnected-(STM32A-PB14-Pad35)") (class "Default")
      (node (ref "STM32") (pin "35") (pinfunction "PB14_35") (pintype "bidirectional"))
    )
    (net (code "71") (name "unconnected-(STM32A-PB15-Pad36)") (class "Default")
      (node (ref "STM32") (pin "36") (pinfunction "PB15_36") (pintype "bidirectional"))
    )
    (net (code "72") (name "unconnected-(STM32A-PC0-Pad8)") (class "Default")
      (node (ref "STM32") (pin "8") (pinfunction "PC0_8") (pintype "bidirectional"))
    )
    (net (code "73") (name "unconnected-(STM32A-PC1-Pad9)") (class "Default")
      (node (ref "STM32") (pin "9") (pinfunction "PC1_9") (pintype "bidirectional"))
    )
    (net (code "74") (name "unconnected-(STM32A-PC6-Pad37)") (class "Default")
      (node (ref "STM32") (pin "37") (pinfunction "PC6_37") (pintype "bidirectional"))
    )
    (net (code "75") (name "unconnected-(STM32A-PC7-Pad38)") (class "Default")
      (node (ref "STM32") (pin "38") (pinfunction "PC7_38") (pintype "bidirectional"))
    )
    (net (code "76") (name "unconnected-(STM32A-PC8-Pad39)") (class "Default")
      (node (ref "STM32") (pin "39") (pinfunction "PC8_39") (pintype "bidirectional"))
    )
    (net (code "77") (name "unconnected-(STM32A-PC9-Pad40)") (class "Default")
      (node (ref "STM32") (pin "40") (pinfunction "PC9_40") (pintype "bidirectional"))
    )
    (net (code "78") (name "unconnected-(STM32A-PC10-Pad51)") (class "Default")
      (node (ref "STM32") (pin "51") (pinfunction "PC10_51") (pintype "bidirectional"))
    )
    (net (code "79") (name "unconnected-(STM32A-PC11-Pad52)") (class "Default")
      (node (ref "STM32") (pin "52") (pinfunction "PC11_52") (pintype "bidirectional"))
    )
    (net (code "80") (name "unconnected-(STM32A-PC12-Pad53)") (class "Default")
      (node (ref "STM32") (pin "53") (pinfunction "PC12_53") (pintype "bidirectional"))
    )
    (net (code "81") (name "unconnected-(STM32A-PC13-Pad2)") (class "Default")
      (node (ref "STM32") (pin "2") (pinfunction "PC13_2") (pintype "bidirectional"))
    )
    (net (code "82") (name "unconnected-(STM32A-PC14{slash}OSC32_IN-Pad3)") (class "Default")
      (node (ref "STM32") (pin "3") (pinfunction "PC14/OSC32_IN_3") (pintype "bidirectional"))
    )
    (net (code "83") (name "unconnected-(STM32A-PC15{slash}OSC32_OUT-Pad4)") (class "Default")
      (node (ref "STM32") (pin "4") (pinfunction "PC15/OSC32_OUT_4") (pintype "bidirectional"))
    )
    (net (code "84") (name "unconnected-(STM32A-PD2-Pad54)") (class "Default")
      (node (ref "STM32") (pin "54") (pinfunction "PD2_54") (pintype "bidirectional"))
    )
    (net (code "85") (name "unconnected-(VREG_33-VOUT_1-Pad2)") (class "Default")
      (node (ref "VREG_33") (pin "2") (pinfunction "VOUT_1_2") (pintype "output"))
    )
  )
)
